# rpi_adapter_2x4L_sink.net
KiCad netlist of a schematic drawn in Altium Designer
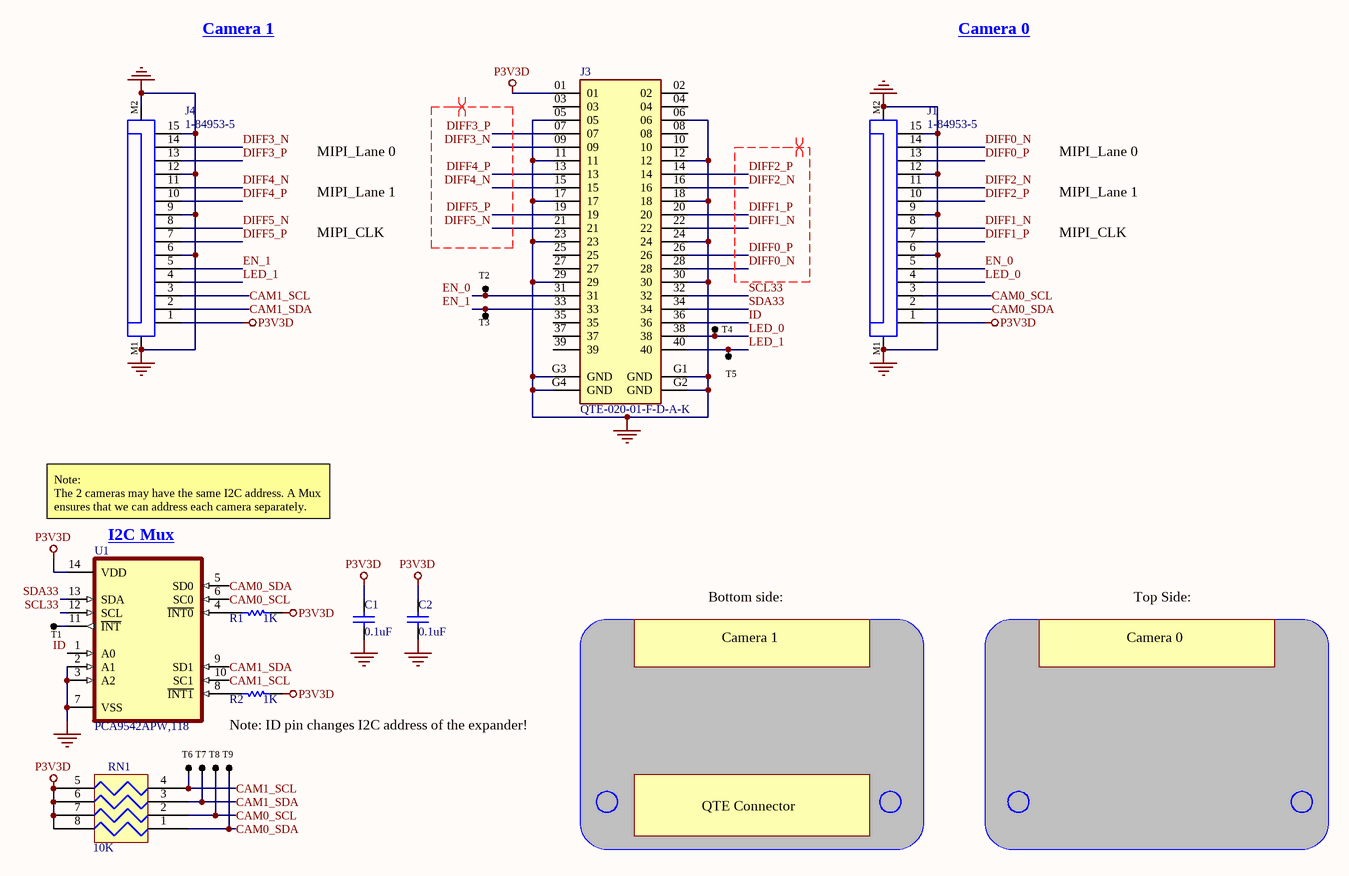
[diagram p0: rpi_adapter_2x4L_sink.SchDoc]

(export (version "E")
  (design (tool "Eeschema 10.0.6"))
  (components
    (comp (ref "C1")
      (value "0.1uF")
      (footprint "CAPC1005X55USR")
      (description "CAP CER 0.1UF 16V X7R 0402")
      (fields
        (field (name "MANUFACTURER PART NUMBER") "CGA2B1X7R1C104K050BC")
        (field (name "MANUFACTURER") "TDK Corporation")
      )
      (libsource (lib "NX Module baseboard") (part "CAP CER 0.1UF 16V X7R 0402"))
    )
    (comp (ref "C2")
      (value "0.1uF")
      (footprint "CAPC1005X55USR")
      (description "CAP CER 0.1UF 16V X7R 0402")
      (fields
        (field (name "MANUFACTURER PART NUMBER") "CGA2B1X7R1C104K050BC")
        (field (name "MANUFACTURER") "TDK Corporation")
      )
      (libsource (lib "NX Module baseboard") (part "CAP CER 0.1UF 16V X7R 0402"))
    )
    (comp (ref "J1")
      (value "1-84953-5")
      (footprint "TE_1-84953-5")
      (description "Conn FPC Connector SKT 15 POS 1mm Solder RA SMD T/R")
      (fields (field (name "MANUFACTURER") "TE Connectivity"))
      (libsource (lib "rpi_adapter") (part "FPC - 15P - 2MP"))
    )
    (comp (ref "J3")
      (value "QTE-020-01-F-D-A-K")
      (footprint "SAMTEC_QTE-020-01-X-D-A")
      (description "Q Strip® High-Speed Ground Plane Header, 0.80mm Pitch")
      (fields
        (field (name "MANUFACTURER") "Samtec")
        (field (name "MANUFACTURER PART NUMBER") "QTE-020-01-F-D-A")
      )
      (libsource (lib "NX Module baseboard") (part "QSE-020-01-F-D-A-K"))
    )
    (comp (ref "J4")
      (value "1-84953-5")
      (footprint "TE_1-84953-5")
      (description "Conn FPC Connector SKT 15 POS 1mm Solder RA SMD T/R")
      (fields (field (name "MANUFACTURER") "TE Connectivity"))
      (libsource (lib "rpi_adapter") (part "FPC - 15P - 2MP"))
    )
    (comp (ref "R1")
      (value "1K")
      (footprint "RESC1005X40USR")
      (description "RES SMD 1K OHM 1% 1/16W 0402")
      (fields
        (field (name "MANUFACTURER") "YAGEO")
        (field (name "MANUFACTURER PART NUMBER") "RC0402FR-071KL")
      )
      (libsource (lib "Tiger_Ti180") (part "RES 1K OHM 1% 1/16W 0402"))
    )
    (comp (ref "R2")
      (value "1K")
      (footprint "RESC1005X40USR")
      (description "RES SMD 1K OHM 1% 1/16W 0402")
      (fields
        (field (name "MANUFACTURER") "YAGEO")
        (field (name "MANUFACTURER PART NUMBER") "RC0402FR-071KL")
      )
      (libsource (lib "Tiger_Ti180") (part "RES 1K OHM 1% 1/16W 0402"))
    )
    (comp (ref "RN1")
      (value "10K")
      (footprint "RESCAXS50P100X200X45-8NA")
      (description "Res Thick Film Array 10K Ohm 5% ±200ppm/°C ISOL 8-Pin 0804(4 X 0402) Convex SMD Automotive T/R")
      (fields
        (field (name "MANUFACTURER") "Panasonic")
        (field (name "MANUFACTURER PART NUMBER") "EXB-28V103JX")
      )
      (libsource (lib "NX Module") (part "RES ARRAY 4 RES 47K OHM 0804"))
    )
    (comp (ref "T1")
      (value "TP_S")
      (footprint "TP 1mm")
      (description "test point")
      (libsource (lib "AiC") (part "TP_S"))
    )
    (comp (ref "T2")
      (value "TP_S")
      (footprint "TP 1mm")
      (description "test point")
      (libsource (lib "AiC") (part "TP_S"))
    )
    (comp (ref "T3")
      (value "TP_S")
      (footprint "TP 1mm")
      (description "test point")
      (libsource (lib "AiC") (part "TP_S"))
    )
    (comp (ref "T4")
      (value "TP_S")
      (footprint "TP 1mm")
      (description "test point")
      (libsource (lib "AiC") (part "TP_S"))
    )
    (comp (ref "T5")
      (value "TP_S")
      (footprint "TP 1mm")
      (description "test point")
      (libsource (lib "AiC") (part "TP_S"))
    )
    (comp (ref "T6")
      (value "TP_S")
      (footprint "TP 1mm")
      (description "test point")
      (libsource (lib "AiC") (part "TP_S"))
    )
    (comp (ref "T7")
      (value "TP_S")
      (footprint "TP 1mm")
      (description "test point")
      (libsource (lib "AiC") (part "TP_S"))
    )
    (comp (ref "T8")
      (value "TP_S")
      (footprint "TP 1mm")
      (description "test point")
      (libsource (lib "AiC") (part "TP_S"))
    )
    (comp (ref "T9")
      (value "TP_S")
      (footprint "TP 1mm")
      (description "test point")
      (libsource (lib "AiC") (part "TP_S"))
    )
    (comp (ref "U1")
      (value "PCA9542APW,118")
      (footprint "SOP65P640X110-14N")
      (description "PCA9542A Series 2-Channel I2C-bus Multiplexer with Interrupt Logic - TSSOP - 14")
      (fields (field (name "MANUFACTURER") "NXP Semiconductors"))
      (libsource (lib "tinyCamera") (part "PCA9542APW,118"))
    )
  )
  (nets
    (net (code "1") (name "/CAM0_SCL") (class "Default")
      (node (ref "J1") (pin "3") (pinfunction "3_3") (pintype "passive"))
      (node (ref "RN1") (pin "2") (pintype "passive"))
      (node (ref "T8") (pin "1") (pintype "passive"))
      (node (ref "U1") (pin "6") (pinfunction "SC0_6") (pintype "input"))
    )
    (net (code "2") (name "/CAM0_SDA") (class "Default")
      (node (ref "J1") (pin "2") (pinfunction "2_2") (pintype "passive"))
      (node (ref "RN1") (pin "1") (pintype "passive"))
      (node (ref "T9") (pin "1") (pintype "passive"))
      (node (ref "U1") (pin "5") (pinfunction "SD0_5") (pintype "input"))
    )
    (net (code "3") (name "/CAM1_SCL") (class "Default")
      (node (ref "J4") (pin "3") (pinfunction "3_3") (pintype "passive"))
      (node (ref "RN1") (pin "4") (pintype "passive"))
      (node (ref "T6") (pin "1") (pintype "passive"))
      (node (ref "U1") (pin "10") (pinfunction "SC1_10") (pintype "input"))
    )
    (net (code "4") (name "/CAM1_SDA") (class "Default")
      (node (ref "J4") (pin "2") (pinfunction "2_2") (pintype "passive"))
      (node (ref "RN1") (pin "3") (pintype "passive"))
      (node (ref "T7") (pin "1") (pintype "passive"))
      (node (ref "U1") (pin "9") (pinfunction "SD1_9") (pintype "input"))
    )
    (net (code "5") (name "/DIFF0_N") (class "Default")
      (node (ref "J1") (pin "14") (pinfunction "14_14") (pintype "passive"))
      (node (ref "J3") (pin "28") (pinfunction "28_28") (pintype "passive"))
    )
    (net (code "6") (name "/DIFF0_P") (class "Default")
      (node (ref "J1") (pin "13") (pinfunction "13_13") (pintype "passive"))
      (node (ref "J3") (pin "26") (pinfunction "26_26") (pintype "passive"))
    )
    (net (code "7") (name "/DIFF1_N") (class "Default")
      (node (ref "J1") (pin "8") (pinfunction "8_8") (pintype "passive"))
      (node (ref "J3") (pin "22") (pinfunction "22_22") (pintype "passive"))
    )
    (net (code "8") (name "/DIFF1_P") (class "Default")
      (node (ref "J1") (pin "7") (pinfunction "7_7") (pintype "passive"))
      (node (ref "J3") (pin "20") (pinfunction "20_20") (pintype "passive"))
    )
    (net (code "9") (name "/DIFF2_N") (class "Default")
      (node (ref "J1") (pin "11") (pinfunction "11_11") (pintype "passive"))
      (node (ref "J3") (pin "16") (pinfunction "16_16") (pintype "passive"))
    )
    (net (code "10") (name "/DIFF2_P") (class "Default")
      (node (ref "J1") (pin "10") (pinfunction "10_10") (pintype "passive"))
      (node (ref "J3") (pin "14") (pinfunction "14_14") (pintype "passive"))
    )
    (net (code "11") (name "/DIFF3_N") (class "Default")
      (node (ref "J3") (pin "09") (pinfunction "09_09") (pintype "passive"))
      (node (ref "J4") (pin "14") (pinfunction "14_14") (pintype "passive"))
    )
    (net (code "12") (name "/DIFF3_P") (class "Default")
      (node (ref "J3") (pin "07") (pinfunction "07_07") (pintype "passive"))
      (node (ref "J4") (pin "13") (pinfunction "13_13") (pintype "passive"))
    )
    (net (code "13") (name "/DIFF4_N") (class "Default")
      (node (ref "J3") (pin "15") (pinfunction "15_15") (pintype "passive"))
      (node (ref "J4") (pin "11") (pinfunction "11_11") (pintype "passive"))
    )
    (net (code "14") (name "/DIFF4_P") (class "Default")
      (node (ref "J3") (pin "13") (pinfunction "13_13") (pintype "passive"))
      (node (ref "J4") (pin "10") (pinfunction "10_10") (pintype "passive"))
    )
    (net (code "15") (name "/DIFF5_N") (class "Default")
      (node (ref "J3") (pin "21") (pinfunction "21_21") (pintype "passive"))
      (node (ref "J4") (pin "8") (pinfunction "8_8") (pintype "passive"))
    )
    (net (code "16") (name "/DIFF5_P") (class "Default")
      (node (ref "J3") (pin "19") (pinfunction "19_19") (pintype "passive"))
      (node (ref "J4") (pin "7") (pinfunction "7_7") (pintype "passive"))
    )
    (net (code "17") (name "/EN_0") (class "Default")
      (node (ref "J1") (pin "5") (pinfunction "5_5") (pintype "passive"))
      (node (ref "J3") (pin "31") (pinfunction "31_31") (pintype "passive"))
      (node (ref "T2") (pin "1") (pintype "passive"))
    )
    (net (code "18") (name "/EN_1") (class "Default")
      (node (ref "J3") (pin "33") (pinfunction "33_33") (pintype "passive"))
      (node (ref "J4") (pin "5") (pinfunction "5_5") (pintype "passive"))
      (node (ref "T3") (pin "1") (pintype "passive"))
    )
    (net (code "19") (name "/ID") (class "Default")
      (node (ref "J3") (pin "36") (pinfunction "36_36") (pintype "passive"))
      (node (ref "U1") (pin "1") (pinfunction "A0_1") (pintype "input"))
    )
    (net (code "20") (name "/LED_0") (class "Default")
      (node (ref "J1") (pin "4") (pinfunction "4_4") (pintype "passive"))
      (node (ref "J3") (pin "38") (pinfunction "38_38") (pintype "passive"))
      (node (ref "T4") (pin "1") (pintype "passive"))
    )
    (net (code "21") (name "/LED_1") (class "Default")
      (node (ref "J3") (pin "40") (pinfunction "40_40") (pintype "passive"))
      (node (ref "J4") (pin "4") (pinfunction "4_4") (pintype "passive"))
      (node (ref "T5") (pin "1") (pintype "passive"))
    )
    (net (code "22") (name "/SCL33") (class "Default")
      (node (ref "J3") (pin "32") (pinfunction "32_32") (pintype "passive"))
      (node (ref "U1") (pin "12") (pinfunction "SCL_12") (pintype "input"))
    )
    (net (code "23") (name "/SDA33") (class "Default")
      (node (ref "J3") (pin "34") (pinfunction "34_34") (pintype "passive"))
      (node (ref "U1") (pin "13") (pinfunction "SDA_13") (pintype "input"))
    )
    (net (code "24") (name "GND") (class "Default")
      (node (ref "C1") (pin "1") (pinfunction "1_1") (pintype "passive"))
      (node (ref "C2") (pin "1") (pinfunction "1_1") (pintype "passive"))
      (node (ref "J1") (pin "12") (pinfunction "12_12") (pintype "passive"))
      (node (ref "J1") (pin "15") (pinfunction "15_15") (pintype "passive"))
      (node (ref "J1") (pin "6") (pinfunction "6_6") (pintype "passive"))
      (node (ref "J1") (pin "9") (pinfunction "9_9") (pintype "passive"))
      (node (ref "J1") (pin "M1") (pinfunction "M1_M1") (pintype "passive"))
      (node (ref "J1") (pin "M2") (pinfunction "M2_M2") (pintype "passive"))
      (node (ref "J3") (pin "05") (pinfunction "05_05") (pintype "passive"))
      (node (ref "J3") (pin "06") (pinfunction "06_06") (pintype "passive"))
      (node (ref "J3") (pin "11") (pinfunction "11_11") (pintype "passive"))
      (node (ref "J3") (pin "12") (pinfunction "12_12") (pintype "passive"))
      (node (ref "J3") (pin "17") (pinfunction "17_17") (pintype "passive"))
      (node (ref "J3") (pin "18") (pinfunction "18_18") (pintype "passive"))
      (node (ref "J3") (pin "23") (pinfunction "23_23") (pintype "passive"))
      (node (ref "J3") (pin "24") (pinfunction "24_24") (pintype "passive"))
      (node (ref "J3") (pin "29") (pinfunction "29_29") (pintype "passive"))
      (node (ref "J3") (pin "30") (pinfunction "30_30") (pintype "passive"))
      (node (ref "J3") (pin "G1") (pinfunction "GND_G1") (pintype "power_in"))
      (node (ref "J3") (pin "G2") (pinfunction "GND_G2") (pintype "power_in"))
      (node (ref "J3") (pin "G3") (pinfunction "GND_G3") (pintype "power_in"))
      (node (ref "J3") (pin "G4") (pinfunction "GND_G4") (pintype "power_in"))
      (node (ref "J4") (pin "12") (pinfunction "12_12") (pintype "passive"))
      (node (ref "J4") (pin "15") (pinfunction "15_15") (pintype "passive"))
      (node (ref "J4") (pin "6") (pinfunction "6_6") (pintype "passive"))
      (node (ref "J4") (pin "9") (pinfunction "9_9") (pintype "passive"))
      (node (ref "J4") (pin "M1") (pinfunction "M1_M1") (pintype "passive"))
      (node (ref "J4") (pin "M2") (pinfunction "M2_M2") (pintype "passive"))
      (node (ref "U1") (pin "2") (pinfunction "A1_2") (pintype "input"))
      (node (ref "U1") (pin "3") (pinfunction "A2_3") (pintype "input"))
      (node (ref "U1") (pin "7") (pinfunction "VSS_7") (pintype "passive"))
    )
    (net (code "25") (name "Net-(U1-~{INT0})") (class "Default")
      (node (ref "R1") (pin "1") (pinfunction "1_1") (pintype "passive"))
      (node (ref "U1") (pin "4") (pinfunction "~{INT0}_4") (pintype "input"))
    )
    (net (code "26") (name "Net-(U1-~{INT1})") (class "Default")
      (node (ref "R2") (pin "1") (pinfunction "1_1") (pintype "passive"))
      (node (ref "U1") (pin "8") (pinfunction "~{INT1}_8") (pintype "input"))
    )
    (net (code "27") (name "Net-(U1-~{INT})") (class "Default")
      (node (ref "T1") (pin "1") (pintype "passive"))
      (node (ref "U1") (pin "11") (pinfunction "~{INT}_11") (pintype "output"))
    )
    (net (code "28") (name "P3V3D") (class "Default")
      (node (ref "C1") (pin "2") (pinfunction "2_2") (pintype "passive"))
      (node (ref "C2") (pin "2") (pinfunction "2_2") (pintype "passive"))
      (node (ref "J1") (pin "1") (pinfunction "1_1") (pintype "passive"))
      (node (ref "J3") (pin "01") (pinfunction "01_01") (pintype "passive"))
      (node (ref "J4") (pin "1") (pinfunction "1_1") (pintype "passive"))
      (node (ref "R1") (pin "2") (pinfunction "2_2") (pintype "passive"))
      (node (ref "R2") (pin "2") (pinfunction "2_2") (pintype "passive"))
      (node (ref "RN1") (pin "5") (pintype "passive"))
      (node (ref "RN1") (pin "6") (pintype "passive"))
      (node (ref "RN1") (pin "7") (pintype "passive"))
      (node (ref "RN1") (pin "8") (pintype "passive"))
      (node (ref "U1") (pin "14") (pinfunction "VDD_14") (pintype "power_in"))
    )
    (net (code "29") (name "unconnected-(J3-Pad02)") (class "Default")
      (node (ref "J3") (pin "02") (pinfunction "02_02") (pintype "passive"))
    )
    (net (code "30") (name "unconnected-(J3-Pad03)") (class "Default")
      (node (ref "J3") (pin "03") (pinfunction "03_03") (pintype "passive"))
    )
    (net (code "31") (name "unconnected-(J3-Pad04)") (class "Default")
      (node (ref "J3") (pin "04") (pinfunction "04_04") (pintype "passive"))
    )
    (net (code "32") (name "unconnected-(J3-Pad08)") (class "Default")
      (node (ref "J3") (pin "08") (pinfunction "08_08") (pintype "passive"))
    )
    (net (code "33") (name "unconnected-(J3-Pad10)") (class "Default")
      (node (ref "J3") (pin "10") (pinfunction "10_10") (pintype "passive"))
    )
    (net (code "34") (name "unconnected-(J3-Pad25)") (class "Default")
      (node (ref "J3") (pin "25") (pinfunction "25_25") (pintype "passive"))
    )
    (net (code "35") (name "unconnected-(J3-Pad27)") (class "Default")
      (node (ref "J3") (pin "27") (pinfunction "27_27") (pintype "passive"))
    )
    (net (code "36") (name "unconnected-(J3-Pad35)") (class "Default")
      (node (ref "J3") (pin "35") (pinfunction "35_35") (pintype "passive"))
    )
    (net (code "37") (name "unconnected-(J3-Pad37)") (class "Default")
      (node (ref "J3") (pin "37") (pinfunction "37_37") (pintype "passive"))
    )
    (net (code "38") (name "unconnected-(J3-Pad39)") (class "Default")
      (node (ref "J3") (pin "39") (pinfunction "39_39") (pintype "passive"))
    )
  )
)
